# logger.net
KiCad netlist of a schematic drawn in EAGLE
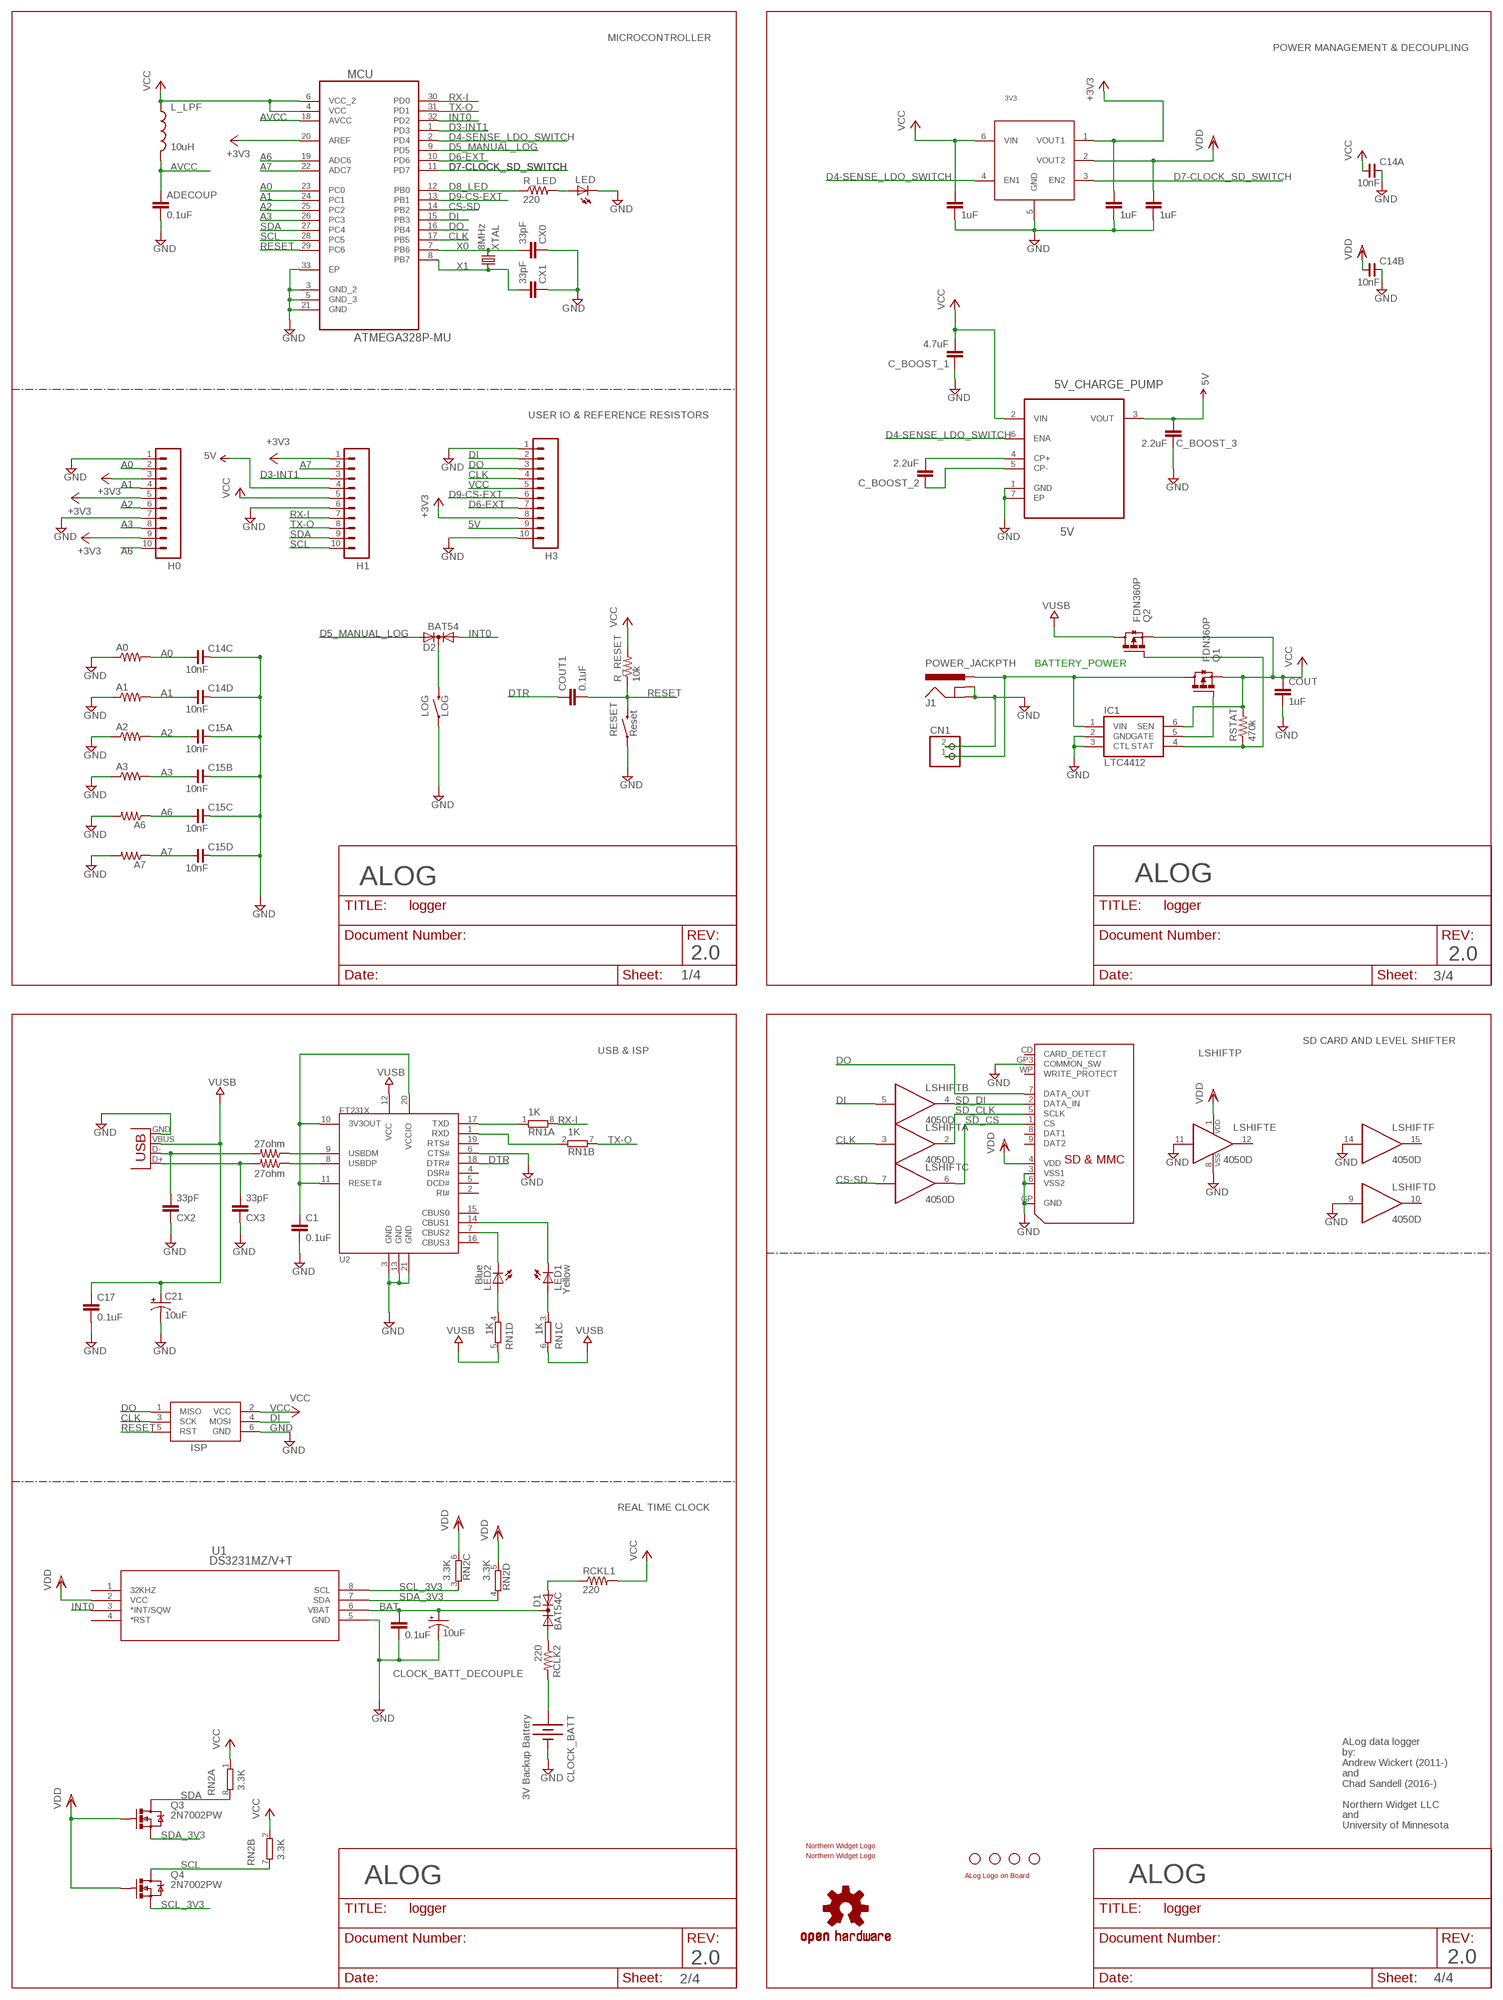
[diagram p0: schematic, sheet 1]

(export (version "E")
  (design (tool "Eeschema 10.0.6"))
  (components
    (comp (ref "3V3")
      (value "MIC5380")
      (footprint "eagle-import:6-TMLF")
      (libsource (lib "eagle-import") (part "MIC5380"))
    )
    (comp (ref "5V_CHARGE_PUMP")
      (value "5V")
      (footprint "eagle-import:SON65P200X200X80-7N")
      (fields (field (name "MPN") "TPS60150DRVR"))
      (libsource (lib "eagle-import") (part "TPS60150DRVR"))
    )
    (comp (ref "A0")
      (value "R-US_0207/10")
      (footprint "eagle-import:0207_10")
      (libsource (lib "eagle-import") (part "resistor_R-US_0207/10"))
    )
    (comp (ref "A1")
      (value "R-US_0207/10")
      (footprint "eagle-import:0207_10")
      (libsource (lib "eagle-import") (part "resistor_R-US_0207/10"))
    )
    (comp (ref "A2")
      (value "R-US_0207/10")
      (footprint "eagle-import:0207_10")
      (libsource (lib "eagle-import") (part "resistor_R-US_0207/10"))
    )
    (comp (ref "A3")
      (value "R-US_0207/10")
      (footprint "eagle-import:0207_10")
      (libsource (lib "eagle-import") (part "resistor_R-US_0207/10"))
    )
    (comp (ref "A6")
      (value "R-US_0207/10")
      (footprint "eagle-import:0207_10")
      (libsource (lib "eagle-import") (part "resistor_R-US_0207/10"))
    )
    (comp (ref "A7")
      (value "R-US_0207/10")
      (footprint "eagle-import:0207_10")
      (libsource (lib "eagle-import") (part "resistor_R-US_0207/10"))
    )
    (comp (ref "ADECOUP")
      (value "0.1uF")
      (footprint "eagle-import:C0603")
      (libsource (lib "eagle-import") (part "resistor_C-EUC0603"))
    )
    (comp (ref "C1")
      (value "0.1uF")
      (footprint "eagle-import:C0603")
      (libsource (lib "eagle-import") (part "resistor_C-EUC0603"))
    )
    (comp (ref "C14")
      (value "10nF")
      (footprint "eagle-import:CECJ-1206")
      (libsource (lib "eagle-import") (part "CCA_ECJ-1206"))
    )
    (comp (ref "C15")
      (value "10nF")
      (footprint "eagle-import:CECJ-1206")
      (libsource (lib "eagle-import") (part "CCA_ECJ-1206"))
    )
    (comp (ref "C17")
      (value "0.1uF")
      (footprint "eagle-import:C0603")
      (libsource (lib "eagle-import") (part "resistor_C-EUC0603"))
    )
    (comp (ref "C21")
      (value "10uF")
      (footprint "eagle-import:EIA3216")
      (libsource (lib "eagle-import") (part "CAP_POL1206"))
    )
    (comp (ref "CLOCK_BATT")
      (value "3V Backup Battery")
      (footprint "eagle-import:BATTCON_12MM_PTH")
      (libsource (lib "eagle-import") (part "BATTERY12PTH"))
    )
    (comp (ref "CLOCK_BATT_DECOUP")
      (value "0.1uF")
      (footprint "eagle-import:C0603")
      (libsource (lib "eagle-import") (part "C-EUC0603"))
    )
    (comp (ref "CLOCK_BATT_DECOUPLE")
      (value "10uF")
      (footprint "eagle-import:EIA3216")
      (libsource (lib "eagle-import") (part "CAP_POL1206"))
    )
    (comp (ref "CLOCK_CIN1")
      (value "1uF")
      (footprint "eagle-import:C0603")
      (libsource (lib "eagle-import") (part "C-EUC0603"))
    )
    (comp (ref "CLOCK_CIN2")
      (value "1uF")
      (footprint "eagle-import:C0603")
      (libsource (lib "eagle-import") (part "C-EUC0603"))
    )
    (comp (ref "CLOCK_CIN3")
      (value "1uF")
      (footprint "eagle-import:C0603")
      (libsource (lib "eagle-import") (part "C-EUC0603"))
    )
    (comp (ref "CN1")
      (value "JST_2PIN-THM")
      (footprint "eagle-import:JST-PH-2-THM")
      (libsource (lib "eagle-import") (part "JST_2PIN-THM"))
    )
    (comp (ref "COUT")
      (value "1uF")
      (footprint "eagle-import:C0603")
      (libsource (lib "eagle-import") (part "C-EUC0603"))
    )
    (comp (ref "COUT1")
      (value "0.1uF")
      (footprint "eagle-import:C0603")
      (libsource (lib "eagle-import") (part "C-EUC0603"))
    )
    (comp (ref "CX0")
      (value "33pF")
      (footprint "eagle-import:C0603")
      (libsource (lib "eagle-import") (part "resistor_C-EUC0603"))
    )
    (comp (ref "CX1")
      (value "33pF")
      (footprint "eagle-import:C0603")
      (libsource (lib "eagle-import") (part "resistor_C-EUC0603"))
    )
    (comp (ref "CX2")
      (value "33pF")
      (footprint "eagle-import:C0603")
      (libsource (lib "eagle-import") (part "resistor_C-EUC0603"))
    )
    (comp (ref "CX3")
      (value "33pF")
      (footprint "eagle-import:C0603")
      (libsource (lib "eagle-import") (part "resistor_C-EUC0603"))
    )
    (comp (ref "C_BOOST_1")
      (value "4.7uF")
      (footprint "eagle-import:C0603")
      (libsource (lib "eagle-import") (part "resistor_C-EUC0603"))
    )
    (comp (ref "C_BOOST_2")
      (value "2.2uF")
      (footprint "eagle-import:C0603")
      (libsource (lib "eagle-import") (part "resistor_C-EUC0603"))
    )
    (comp (ref "C_BOOST_3")
      (value "2.2uF")
      (footprint "eagle-import:C0603")
      (libsource (lib "eagle-import") (part "resistor_C-EUC0603"))
    )
    (comp (ref "D+")
      (value "27ohm")
      (footprint "eagle-import:R0603")
      (libsource (lib "eagle-import") (part "R-US_R0603"))
    )
    (comp (ref "D-")
      (value "27ohm")
      (footprint "eagle-import:R0603")
      (libsource (lib "eagle-import") (part "R-US_R0603"))
    )
    (comp (ref "D1")
      (value "BAT54C")
      (footprint "eagle-import:SOT23C")
      (libsource (lib "eagle-import") (part "DIODE_AC-CA_"))
    )
    (comp (ref "D2")
      (value "BAT54")
      (footprint "eagle-import:SOT23C")
      (libsource (lib "eagle-import") (part "DIODE_AC-CA_"))
    )
    (comp (ref "H0")
      (value "M10-3.5MM")
      (footprint "eagle-import:SCREWTERMINAL-3.5MM-8")
      (libsource (lib "eagle-import") (part "M10-3.5MM"))
    )
    (comp (ref "H1")
      (value "M10-3.5MM")
      (footprint "eagle-import:SCREWTERMINAL-3.5MM-8")
      (libsource (lib "eagle-import") (part "M10-3.5MM"))
    )
    (comp (ref "H3")
      (value "M10-3.5MM")
      (footprint "eagle-import:SCREWTERMINAL-3.5MM-8")
      (libsource (lib "eagle-import") (part "M10-3.5MM"))
    )
    (comp (ref "IC1")
      (value "LTC4412")
      (footprint "eagle-import:TSOT23-6")
      (libsource (lib "eagle-import") (part "LTC4412S6E"))
    )
    (comp (ref "ISP")
      (value "AVRISP-6")
      (footprint "eagle-import:AVRISP")
      (libsource (lib "eagle-import") (part "AVRISP-6"))
    )
    (comp (ref "J1")
      (value "POWER_JACKPTH")
      (footprint "eagle-import:POWER_JACK_PTH")
      (libsource (lib "eagle-import") (part "POWER_JACKPTH"))
    )
    (comp (ref "JP1")
      (value "STAND-OFF")
      (footprint "eagle-import:STAND-OFF")
      (libsource (lib "eagle-import") (part "STAND-OFF"))
    )
    (comp (ref "JP2")
      (value "STAND-OFF")
      (footprint "eagle-import:STAND-OFF")
      (libsource (lib "eagle-import") (part "STAND-OFF"))
    )
    (comp (ref "JP3")
      (value "STAND-OFF")
      (footprint "eagle-import:STAND-OFF")
      (libsource (lib "eagle-import") (part "STAND-OFF"))
    )
    (comp (ref "JP4")
      (value "STAND-OFF")
      (footprint "eagle-import:STAND-OFF")
      (libsource (lib "eagle-import") (part "STAND-OFF"))
    )
    (comp (ref "JP5")
      (value "USB-B")
      (footprint "eagle-import:USB-B-PTH")
      (libsource (lib "eagle-import") (part "USBPTH"))
    )
    (comp (ref "LED")
      (value "LED3MM")
      (footprint "eagle-import:LED3MM")
      (libsource (lib "eagle-import") (part "LED3MM"))
    )
    (comp (ref "LED1")
      (value "Yellow")
      (footprint "eagle-import:LED-0603")
      (libsource (lib "eagle-import") (part "SparkFun-LED_LED0603"))
    )
    (comp (ref "LED2")
      (value "Blue")
      (footprint "eagle-import:LED-0603")
      (libsource (lib "eagle-import") (part "SparkFun-LED_LED0603"))
    )
    (comp (ref "LOG")
      (value "LOG")
      (footprint "eagle-import:TACTILE-PTH")
      (libsource (lib "eagle-import") (part "SWITCH-MOMENTARY-2PTH"))
    )
    (comp (ref "LOGO1")
      (value "OSHW-LOGOM")
      (footprint "eagle-import:OSHW-LOGO-M")
      (libsource (lib "eagle-import") (part "OSHW-LOGOM"))
    )
    (comp (ref "LSHIFT")
      (value "4050D")
      (footprint "eagle-import:SO16")
      (libsource (lib "eagle-import") (part "4050D"))
    )
    (comp (ref "L_LPF")
      (value "10uH")
      (footprint "eagle-import:0805")
      (libsource (lib "eagle-import") (part "INDUCTOR0805"))
    )
    (comp (ref "MCU")
      (value "ATMEGA328P-MU")
      (footprint "eagle-import:QFN50P500X500X100-33N")
      (libsource (lib "eagle-import") (part "ATMEGA328P-MU"))
    )
    (comp (ref "Q1")
      (value "FDN360P")
      (footprint "eagle-import:SUPER-SOT3")
      (libsource (lib "eagle-import") (part "FDN360P"))
    )
    (comp (ref "Q2")
      (value "FDN360P")
      (footprint "eagle-import:SUPER-SOT3")
      (libsource (lib "eagle-import") (part "FDN360P"))
    )
    (comp (ref "Q3")
      (value "2N7002PW")
      (footprint "eagle-import:SOT323")
      (libsource (lib "eagle-import") (part "MOSFET-NCHANNELSOT323"))
    )
    (comp (ref "Q4")
      (value "2N7002PW")
      (footprint "eagle-import:SOT323")
      (libsource (lib "eagle-import") (part "MOSFET-NCHANNELSOT323"))
    )
    (comp (ref "RCKL1")
      (value "220")
      (footprint "eagle-import:R0603")
      (libsource (lib "eagle-import") (part "R-US_R0603"))
    )
    (comp (ref "RCLK2")
      (value "220")
      (footprint "eagle-import:R0603")
      (libsource (lib "eagle-import") (part "R-US_R0603"))
    )
    (comp (ref "RESET")
      (value "Reset")
      (footprint "eagle-import:TACTILE-PTH")
      (libsource (lib "eagle-import") (part "SWITCH-MOMENTARY-2PTH"))
    )
    (comp (ref "RN1")
      (value "1K")
      (footprint "eagle-import:0603-ARC")
      (libsource (lib "eagle-import") (part "4R-N0603-ARC"))
    )
    (comp (ref "RN2")
      (value "3.3K")
      (footprint "eagle-import:0603-ARC")
      (libsource (lib "eagle-import") (part "4R-N0603-ARC"))
    )
    (comp (ref "RSTAT")
      (value "470k")
      (footprint "eagle-import:R0603")
      (libsource (lib "eagle-import") (part "R-US_R0603"))
    )
    (comp (ref "R_LED")
      (value "220")
      (footprint "eagle-import:R0603")
      (libsource (lib "eagle-import") (part "resistor_R-US_R0603"))
    )
    (comp (ref "R_RESET")
      (value "10k")
      (footprint "eagle-import:R0603")
      (libsource (lib "eagle-import") (part "R-US_R0603"))
    )
    (comp (ref "SD")
      (value "SDMMC06132")
      (footprint "eagle-import:06132")
      (libsource (lib "eagle-import") (part "SDMMC06132"))
    )
    (comp (ref "U$1")
      (value "NWLOGO")
      (footprint "eagle-import:NWLOGO")
      (libsource (lib "eagle-import") (part "NWLOGO"))
    )
    (comp (ref "U$2")
      (value "ALOG_LOGO_V1_5.5MM")
      (footprint "eagle-import:ALOG_LOGO_V1_SMALL")
      (libsource (lib "eagle-import") (part "ALOG_LOGO_V1_5.5MM"))
    )
    (comp (ref "U$3")
      (value "NWLOGO_MED")
      (footprint "eagle-import:NWLOGO_MED")
      (libsource (lib "eagle-import") (part "NWLOGO_MED"))
    )
    (comp (ref "U1")
      (value "DS3231MZ/V+T")
      (footprint "eagle-import:21-0041B_8")
      (libsource (lib "eagle-import") (part "DS3231MZ/V+T"))
    )
    (comp (ref "U2")
      (value "FT231X-Q")
      (footprint "eagle-import:QFN20")
      (libsource (lib "eagle-import") (part "FT231X-Q"))
    )
    (comp (ref "XTAL")
      (value "8MHz")
      (footprint "eagle-import:HC49U-V")
      (libsource (lib "eagle-import") (part "CRYSTALHC49UV"))
    )
  )
  (nets
    (net (code "1") (name "+3V3") (class "Default")
      (node (ref "3V3") (pin "1") (pinfunction "VOUT1_1") (pintype "power_in"))
      (node (ref "CLOCK_CIN2") (pin "1") (pinfunction "1_1") (pintype "passive"))
      (node (ref "H0") (pin "3") (pinfunction "3_3") (pintype "passive"))
      (node (ref "H0") (pin "5") (pinfunction "5_5") (pintype "passive"))
      (node (ref "H0") (pin "9") (pinfunction "9_9") (pintype "passive"))
      (node (ref "H1") (pin "1") (pinfunction "1_1") (pintype "passive"))
      (node (ref "H3") (pin "8") (pinfunction "8_8") (pintype "passive"))
      (node (ref "MCU") (pin "20") (pinfunction "AREF_20") (pintype "input"))
    )
    (net (code "2") (name "/A0") (class "Default")
      (node (ref "A0") (pin "2") (pinfunction "2_2") (pintype "passive"))
      (node (ref "C14") (pin "C1") (pinfunction "1_C1") (pintype "passive"))
      (node (ref "H0") (pin "2") (pinfunction "2_2") (pintype "passive"))
      (node (ref "MCU") (pin "23") (pinfunction "PC0_23") (pintype "bidirectional"))
    )
    (net (code "3") (name "/A1") (class "Default")
      (node (ref "A1") (pin "2") (pinfunction "2_2") (pintype "passive"))
      (node (ref "C14") (pin "D1") (pinfunction "1_D1") (pintype "passive"))
      (node (ref "H0") (pin "4") (pinfunction "4_4") (pintype "passive"))
      (node (ref "MCU") (pin "24") (pinfunction "PC1_24") (pintype "bidirectional"))
    )
    (net (code "4") (name "/A2") (class "Default")
      (node (ref "A2") (pin "2") (pinfunction "2_2") (pintype "passive"))
      (node (ref "C15") (pin "A1") (pinfunction "1_A1") (pintype "passive"))
      (node (ref "H0") (pin "6") (pinfunction "6_6") (pintype "passive"))
      (node (ref "MCU") (pin "25") (pinfunction "PC2_25") (pintype "bidirectional"))
    )
    (net (code "5") (name "/A3") (class "Default")
      (node (ref "A3") (pin "2") (pinfunction "2_2") (pintype "passive"))
      (node (ref "C15") (pin "B1") (pinfunction "1_B1") (pintype "passive"))
      (node (ref "H0") (pin "8") (pinfunction "8_8") (pintype "passive"))
      (node (ref "MCU") (pin "26") (pinfunction "PC3_26") (pintype "bidirectional"))
    )
    (net (code "6") (name "/A6") (class "Default")
      (node (ref "A6") (pin "1") (pinfunction "1_1") (pintype "passive"))
      (node (ref "C15") (pin "C1") (pinfunction "1_C1") (pintype "passive"))
      (node (ref "H0") (pin "10") (pinfunction "10_10") (pintype "passive"))
      (node (ref "MCU") (pin "19") (pinfunction "ADC6_19") (pintype "input"))
    )
    (net (code "7") (name "/A7") (class "Default")
      (node (ref "A7") (pin "1") (pinfunction "1_1") (pintype "passive"))
      (node (ref "C15") (pin "D1") (pinfunction "1_D1") (pintype "passive"))
      (node (ref "H1") (pin "2") (pinfunction "2_2") (pintype "passive"))
      (node (ref "MCU") (pin "22") (pinfunction "ADC7_22") (pintype "input"))
    )
    (net (code "8") (name "/AVCC") (class "Default")
      (node (ref "ADECOUP") (pin "1") (pinfunction "1_1") (pintype "passive"))
      (node (ref "L_LPF") (pin "2") (pinfunction "2_2") (pintype "passive"))
      (node (ref "MCU") (pin "18") (pinfunction "AVCC_18") (pintype "power_in"))
    )
    (net (code "9") (name "/BAT") (class "Default")
      (node (ref "CLOCK_BATT_DECOUP") (pin "1") (pinfunction "1_1") (pintype "passive"))
      (node (ref "CLOCK_BATT_DECOUPLE") (pin "A") (pinfunction "+_A") (pintype "passive"))
      (node (ref "D1") (pin "3") (pinfunction "K_3") (pintype "passive"))
      (node (ref "U1") (pin "6") (pinfunction "VBAT_6") (pintype "power_in"))
    )
    (net (code "10") (name "/CLK") (class "Default")
      (node (ref "H3") (pin "4") (pinfunction "4_4") (pintype "passive"))
      (node (ref "ISP") (pin "3") (pinfunction "SCK_3") (pintype "output"))
      (node (ref "LSHIFT") (pin "3") (pinfunction "I_3") (pintype "input"))
      (node (ref "MCU") (pin "17") (pinfunction "PB5_17") (pintype "bidirectional"))
    )
    (net (code "11") (name "/CS-SD") (class "Default")
      (node (ref "LSHIFT") (pin "7") (pinfunction "I_7") (pintype "input"))
      (node (ref "MCU") (pin "14") (pinfunction "PB2_14") (pintype "bidirectional"))
    )
    (net (code "12") (name "/D3-INT1") (class "Default")
      (node (ref "H1") (pin "3") (pinfunction "3_3") (pintype "passive"))
      (node (ref "MCU") (pin "1") (pinfunction "PD3_1") (pintype "bidirectional"))
    )
    (net (code "13") (name "/D4-SENSE_LDO_SWITCH") (class "Default")
      (node (ref "3V3") (pin "4") (pinfunction "EN1_4") (pintype "input"))
      (node (ref "5V_CHARGE_PUMP") (pin "6") (pinfunction "ENA_6") (pintype "input"))
      (node (ref "MCU") (pin "2") (pinfunction "PD4_2") (pintype "bidirectional"))
    )
    (net (code "14") (name "/D5_MANUAL_LOG") (class "Default")
      (node (ref "D2") (pin "2") (pinfunction "A2_2") (pintype "passive"))
      (node (ref "MCU") (pin "9") (pinfunction "PD5_9") (pintype "bidirectional"))
    )
    (net (code "15") (name "/D6-EXT") (class "Default")
      (node (ref "H3") (pin "7") (pinfunction "7_7") (pintype "passive"))
      (node (ref "MCU") (pin "10") (pinfunction "PD6_10") (pintype "bidirectional"))
    )
    (net (code "16") (name "/D7-CLOCK_SD_SWITCH") (class "Default")
      (node (ref "3V3") (pin "3") (pinfunction "EN2_3") (pintype "input"))
      (node (ref "MCU") (pin "11") (pinfunction "PD7_11") (pintype "bidirectional"))
    )
    (net (code "17") (name "/D8_LED") (class "Default")
      (node (ref "MCU") (pin "12") (pinfunction "PB0_12") (pintype "bidirectional"))
      (node (ref "R_LED") (pin "1") (pinfunction "1_1") (pintype "passive"))
    )
    (net (code "18") (name "/D9-CS-EXT") (class "Default")
      (node (ref "H3") (pin "6") (pinfunction "6_6") (pintype "passive"))
      (node (ref "MCU") (pin "13") (pinfunction "PB1_13") (pintype "bidirectional"))
    )
    (net (code "19") (name "/DI") (class "Default")
      (node (ref "H3") (pin "2") (pinfunction "2_2") (pintype "passive"))
      (node (ref "ISP") (pin "4") (pinfunction "MOSI_4") (pintype "output"))
      (node (ref "LSHIFT") (pin "5") (pinfunction "I_5") (pintype "input"))
      (node (ref "MCU") (pin "15") (pinfunction "PB3_15") (pintype "bidirectional"))
    )
    (net (code "20") (name "/DO") (class "Default")
      (node (ref "H3") (pin "3") (pinfunction "3_3") (pintype "passive"))
      (node (ref "ISP") (pin "1") (pinfunction "MISO_1") (pintype "input"))
      (node (ref "MCU") (pin "16") (pinfunction "PB4_16") (pintype "bidirectional"))
      (node (ref "SD") (pin "7") (pinfunction "DATA_OUT_7") (pintype "output"))
    )
    (net (code "21") (name "/DTR") (class "Default")
      (node (ref "COUT1") (pin "1") (pinfunction "1_1") (pintype "passive"))
      (node (ref "U2") (pin "18") (pinfunction "DTR#_18") (pintype "bidirectional"))
    )
    (net (code "22") (name "/INT0") (class "Default")
      (node (ref "D2") (pin "1") (pinfunction "A1_1") (pintype "passive"))
      (node (ref "MCU") (pin "32") (pinfunction "PD2_32") (pintype "bidirectional"))
      (node (ref "U1") (pin "3") (pinfunction "*INT/SQW_3") (pintype "passive"))
    )
    (net (code "23") (name "/RESET") (class "Default")
      (node (ref "COUT1") (pin "2") (pinfunction "2_2") (pintype "passive"))
      (node (ref "ISP") (pin "5") (pinfunction "RST_5") (pintype "output"))
      (node (ref "MCU") (pin "29") (pinfunction "PC6_29") (pintype "bidirectional"))
      (node (ref "RESET") (pin "3") (pinfunction "2_3") (pintype "passive"))
      (node (ref "R_RESET") (pin "1") (pinfunction "1_1") (pintype "passive"))
    )
    (net (code "24") (name "/RX-I") (class "Default")
      (node (ref "H1") (pin "7") (pinfunction "7_7") (pintype "passive"))
      (node (ref "MCU") (pin "30") (pinfunction "PD0_30") (pintype "bidirectional"))
      (node (ref "RN1") (pin "8") (pinfunction "2_8") (pintype "passive"))
    )
    (net (code "25") (name "/SCL") (class "Default")
      (node (ref "H1") (pin "10") (pinfunction "10_10") (pintype "passive"))
      (node (ref "MCU") (pin "28") (pinfunction "PC5_28") (pintype "bidirectional"))
      (node (ref "Q4") (pin "3") (pinfunction "D_3") (pintype "passive"))
      (node (ref "RN2") (pin "7") (pinfunction "2_7") (pintype "passive"))
    )
    (net (code "26") (name "/SCL_3V3") (class "Default")
      (node (ref "Q4") (pin "2") (pinfunction "S_2") (pintype "passive"))
      (node (ref "RN2") (pin "3") (pinfunction "1_3") (pintype "passive"))
      (node (ref "U1") (pin "8") (pinfunction "SCL_8") (pintype "passive"))
    )
    (net (code "27") (name "/SDA") (class "Default")
      (node (ref "H1") (pin "9") (pinfunction "9_9") (pintype "passive"))
      (node (ref "MCU") (pin "27") (pinfunction "PC4_27") (pintype "bidirectional"))
      (node (ref "Q3") (pin "3") (pinfunction "D_3") (pintype "passive"))
      (node (ref "RN2") (pin "8") (pinfunction "2_8") (pintype "passive"))
    )
    (net (code "28") (name "/SDA_3V3") (class "Default")
      (node (ref "Q3") (pin "2") (pinfunction "S_2") (pintype "passive"))
      (node (ref "RN2") (pin "4") (pinfunction "1_4") (pintype "passive"))
      (node (ref "U1") (pin "7") (pinfunction "SDA_7") (pintype "passive"))
    )
    (net (code "29") (name "/SD_CLK") (class "Default")
      (node (ref "LSHIFT") (pin "2") (pinfunction "O_2") (pintype "output"))
      (node (ref "SD") (pin "5") (pinfunction "SCLK_5") (pintype "input"))
    )
    (net (code "30") (name "/SD_CS") (class "Default")
      (node (ref "LSHIFT") (pin "6") (pinfunction "O_6") (pintype "output"))
      (node (ref "SD") (pin "1") (pinfunction "CS_1") (pintype "input"))
    )
    (net (code "31") (name "/SD_DI") (class "Default")
      (node (ref "LSHIFT") (pin "4") (pinfunction "O_4") (pintype "output"))
      (node (ref "SD") (pin "2") (pinfunction "DATA_IN_2") (pintype "input"))
    )
    (net (code "32") (name "/TX-O") (class "Default")
      (node (ref "H1") (pin "8") (pinfunction "8_8") (pintype "passive"))
      (node (ref "MCU") (pin "31") (pinfunction "PD1_31") (pintype "bidirectional"))
      (node (ref "RN1") (pin "7") (pinfunction "2_7") (pintype "passive"))
    )
    (net (code "33") (name "/X0") (class "Default")
      (node (ref "CX0") (pin "2") (pinfunction "2_2") (pintype "passive"))
      (node (ref "MCU") (pin "7") (pinfunction "PB6_7") (pintype "bidirectional"))
      (node (ref "XTAL") (pin "2") (pinfunction "2_2") (pintype "passive"))
    )
    (net (code "34") (name "/X1") (class "Default")
      (node (ref "CX1") (pin "2") (pinfunction "2_2") (pintype "passive"))
      (node (ref "MCU") (pin "8") (pinfunction "PB7_8") (pintype "bidirectional"))
      (node (ref "XTAL") (pin "1") (pinfunction "1_1") (pintype "passive"))
    )
    (net (code "35") (name "5V") (class "Default")
      (node (ref "5V_CHARGE_PUMP") (pin "3") (pinfunction "VOUT_3") (pintype "output"))
      (node (ref "C_BOOST_3") (pin "2") (pinfunction "2_2") (pintype "passive"))
      (node (ref "H1") (pin "4") (pinfunction "4_4") (pintype "passive"))
      (node (ref "H3") (pin "9") (pinfunction "9_9") (pintype "passive"))
    )
    (net (code "36") (name "GND") (class "Default")
      (node (ref "3V3") (pin "5") (pinfunction "GND_5") (pintype "power_in"))
      (node (ref "5V_CHARGE_PUMP") (pin "1") (pinfunction "GND_1") (pintype "passive"))
      (node (ref "5V_CHARGE_PUMP") (pin "7") (pinfunction "EP_7") (pintype "passive"))
      (node (ref "A0") (pin "1") (pinfunction "1_1") (pintype "passive"))
      (node (ref "A1") (pin "1") (pinfunction "1_1") (pintype "passive"))
      (node (ref "A2") (pin "1") (pinfunction "1_1") (pintype "passive"))
      (node (ref "A3") (pin "1") (pinfunction "1_1") (pintype "passive"))
      (node (ref "A6") (pin "2") (pinfunction "2_2") (pintype "passive"))
      (node (ref "A7") (pin "2") (pinfunction "2_2") (pintype "passive"))
      (node (ref "ADECOUP") (pin "2") (pinfunction "2_2") (pintype "passive"))
      (node (ref "C1") (pin "2") (pinfunction "2_2") (pintype "passive"))
      (node (ref "C14") (pin "A2") (pinfunction "2_A2") (pintype "passive"))
      (node (ref "C14") (pin "B2") (pinfunction "2_B2") (pintype "passive"))
      (node (ref "C14") (pin "C2") (pinfunction "2_C2") (pintype "passive"))
      (node (ref "C14") (pin "D2") (pinfunction "2_D2") (pintype "passive"))
      (node (ref "C15") (pin "A2") (pinfunction "2_A2") (pintype "passive"))
      (node (ref "C15") (pin "B2") (pinfunction "2_B2") (pintype "passive"))
      (node (ref "C15") (pin "C2") (pinfunction "2_C2") (pintype "passive"))
      (node (ref "C15") (pin "D2") (pinfunction "2_D2") (pintype "passive"))
      (node (ref "C17") (pin "2") (pinfunction "2_2") (pintype "passive"))
      (node (ref "C21") (pin "C") (pinfunction "-_C") (pintype "passive"))
      (node (ref "CLOCK_BATT") (pin "GND") (pinfunction "-_GND") (pintype "power_in"))
      (node (ref "CLOCK_BATT_DECOUP") (pin "2") (pinfunction "2_2") (pintype "passive"))
      (node (ref "CLOCK_BATT_DECOUPLE") (pin "C") (pinfunction "-_C") (pintype "passive"))
      (node (ref "CLOCK_CIN1") (pin "2") (pinfunction "2_2") (pintype "passive"))
      (node (ref "CLOCK_CIN2") (pin "2") (pinfunction "2_2") (pintype "passive"))
      (node (ref "CLOCK_CIN3") (pin "2") (pinfunction "2_2") (pintype "passive"))
      (node (ref "CN1") (pin "2") (pinfunction "1_2") (pintype "passive"))
      (node (ref "COUT") (pin "2") (pinfunction "2_2") (pintype "passive"))
      (node (ref "CX0") (pin "1") (pinfunction "1_1") (pintype "passive"))
      (node (ref "CX1") (pin "1") (pinfunction "1_1") (pintype "passive"))
      (node (ref "CX2") (pin "1") (pinfunction "1_1") (pintype "passive"))
      (node (ref "CX3") (pin "1") (pinfunction "1_1") (pintype "passive"))
      (node (ref "C_BOOST_1") (pin "1") (pinfunction "1_1") (pintype "passive"))
      (node (ref "C_BOOST_3") (pin "1") (pinfunction "1_1") (pintype "passive"))
      (node (ref "H0") (pin "1") (pinfunction "1_1") (pintype "passive"))
      (node (ref "H0") (pin "7") (pinfunction "7_7") (pintype "passive"))
      (node (ref "H1") (pin "6") (pinfunction "6_6") (pintype "passive"))
      (node (ref "H3") (pin "1") (pinfunction "1_1") (pintype "passive"))
      (node (ref "H3") (pin "10") (pinfunction "10_10") (pintype "passive"))
      (node (ref "IC1") (pin "2") (pinfunction "GND_2") (pintype "passive"))
      (node (ref "IC1") (pin "3") (pinfunction "CTL_3") (pintype "input"))
      (node (ref "ISP") (pin "6") (pinfunction "GND_6") (pintype "power_in"))
      (node (ref "J1") (pin "GND") (pinfunction "GND_GND") (pintype "bidirectional"))
      (node (ref "J1") (pin "GNDBREAK") (pinfunction "GNDBREAK_GNDBREAK") (pintype "bidirectional"))
      (node (ref "JP5") (pin "GND") (pinfunction "GND_GND") (pintype "bidirectional"))
      (node (ref "LED") (pin "K") (pinfunction "C_K") (pintype "passive"))
      (node (ref "LOG") (pin "1") (pinfunction "1_1") (pintype "passive"))
      (node (ref "LSHIFT") (pin "11") (pinfunction "I_11") (pintype "input"))
      (node (ref "LSHIFT") (pin "14") (pinfunction "I_14") (pintype "input"))
      (node (ref "LSHIFT") (pin "8") (pinfunction "VSS_8") (pintype "power_in"))
      (node (ref "LSHIFT") (pin "9") (pinfunction "I_9") (pintype "input"))
      (node (ref "MCU") (pin "21") (pinfunction "GND_21") (pintype "passive"))
      (node (ref "MCU") (pin "3") (pinfunction "GND_2_3") (pintype "passive"))
      (node (ref "MCU") (pin "33") (pinfunction "EP_33") (pintype "passive"))
      (node (ref "MCU") (pin "5") (pinfunction "GND_3_5") (pintype "passive"))
      (node (ref "RESET") (pin "1") (pinfunction "1_1") (pintype "passive"))
      (node (ref "SD") (pin "3") (pinfunction "VSS1_3") (pintype "power_in"))
      (node (ref "SD") (pin "6") (pinfunction "VSS2_6") (pintype "power_in"))
      (node (ref "SD") (pin "GP") (pinfunction "GND_GP") (pintype "power_in"))
      (node (ref "SD") (pin "GP3") (pinfunction "COMMON_SW_GP3") (pintype "passive"))
      (node (ref "U1") (pin "5") (pinfunction "GND_5") (pintype "power_in"))
      (node (ref "U2") (pin "13") (pinfunction "GND_13") (pintype "bidirectional"))
      (node (ref "U2") (pin "21") (pinfunction "GND_21") (pintype "bidirectional"))
      (node (ref "U2") (pin "3") (pinfunction "GND_3") (pintype "bidirectional"))
      (node (ref "U2") (pin "6") (pinfunction "CTS#_6") (pintype "bidirectional"))
    )
    (net (code "37") (name "Net-(5V_CHARGE_PUMP-CP+)") (class "Default")
      (node (ref "5V_CHARGE_PUMP") (pin "4") (pinfunction "CP+_4") (pintype "passive"))
      (node (ref "C_BOOST_2") (pin "2") (pinfunction "2_2") (pintype "passive"))
    )
    (net (code "38") (name "Net-(5V_CHARGE_PUMP-CP-)") (class "Default")
      (node (ref "5V_CHARGE_PUMP") (pin "5") (pinfunction "CP-_5") (pintype "passive"))
      (node (ref "C_BOOST_2") (pin "1") (pinfunction "1_1") (pintype "passive"))
    )
    (net (code "39") (name "Net-(CLOCK_BATT-+)") (class "Default")
      (node (ref "CLOCK_BATT") (pin "VCC@1") (pinfunction "+_VCC@1") (pintype "power_in"))
      (node (ref "RCLK2") (pin "2") (pinfunction "2_2") (pintype "passive"))
    )
    (net (code "40") (name "Net-(CN1-2)") (class "Default")
      (node (ref "CN1") (pin "1") (pinfunction "2_1") (pintype "passive"))
      (node (ref "IC1") (pin "1") (pinfunction "VIN_1") (pintype "input"))
      (node (ref "J1") (pin "PWR") (pinfunction "PWR_PWR") (pintype "bidirectional"))
      (node (ref "Q1") (pin "3") (pinfunction "D_3") (pintype "passive"))
    )
    (net (code "41") (name "Net-(CX2-Pad2)") (class "Default")
      (node (ref "CX2") (pin "2") (pinfunction "2_2") (pintype "passive"))
      (node (ref "D-") (pin "2") (pinfunction "2_2") (pintype "passive"))
      (node (ref "JP5") (pin "D-") (pinfunction "D-_D-") (pintype "bidirectional"))
    )
    (net (code "42") (name "Net-(CX3-Pad2)") (class "Default")
      (node (ref "CX3") (pin "2") (pinfunction "2_2") (pintype "passive"))
      (node (ref "D+") (pin "2") (pinfunction "2_2") (pintype "passive"))
      (node (ref "JP5") (pin "D+") (pinfunction "D+_D+") (pintype "bidirectional"))
    )
    (net (code "43") (name "Net-(D1-A1)") (class "Default")
      (node (ref "D1") (pin "1") (pinfunction "A1_1") (pintype "passive"))
      (node (ref "RCLK2") (pin "1") (pinfunction "1_1") (pintype "passive"))
    )
    (net (code "44") (name "Net-(D1-A2)") (class "Default")
      (node (ref "D1") (pin "2") (pinfunction "A2_2") (pintype "passive"))
      (node (ref "RCKL1") (pin "1") (pinfunction "1_1") (pintype "passive"))
    )
    (net (code "45") (name "Net-(D2-K)") (class "Default")
      (node (ref "D2") (pin "3") (pinfunction "K_3") (pintype "passive"))
      (node (ref "LOG") (pin "3") (pinfunction "2_3") (pintype "passive"))
    )
    (net (code "46") (name "Net-(IC1-GATE)") (class "Default")
      (node (ref "IC1") (pin "5") (pinfunction "GATE_5") (pintype "output"))
      (node (ref "Q1") (pin "1") (pinfunction "G_1") (pintype "passive"))
    )
    (net (code "47") (name "Net-(IC1-STAT)") (class "Default")
      (node (ref "IC1") (pin "4") (pinfunction "STAT_4") (pintype "open_collector"))
      (node (ref "Q2") (pin "1") (pinfunction "G_1") (pintype "passive"))
      (node (ref "RSTAT") (pin "1") (pinfunction "1_1") (pintype "passive"))
    )
    (net (code "48") (name "Net-(LED-PadA)") (class "Default")
      (node (ref "LED") (pin "A") (pinfunction "A_A") (pintype "passive"))
      (node (ref "R_LED") (pin "2") (pinfunction "2_2") (pintype "passive"))
    )
    (net (code "49") (name "Net-(RN1B-1)") (class "Default")
      (node (ref "RN1") (pin "2") (pinfunction "1_2") (pintype "passive"))
      (node (ref "U2") (pin "1") (pinfunction "RXD_1") (pintype "bidirectional"))
    )
    (net (code "50") (name "Net-(RN1C-1)") (class "Default")
      (node (ref "LED1") (pin "A") (pinfunction "A_A") (pintype "passive"))
      (node (ref "RN1") (pin "3") (pinfunction "1_3") (pintype "passive"))
    )
    (net (code "51") (name "Net-(RN1D-1)") (class "Default")
      (node (ref "LED2") (pin "A") (pinfunction "A_A") (pintype "passive"))
      (node (ref "RN1") (pin "4") (pinfunction "1_4") (pintype "passive"))
    )
    (net (code "52") (name "Net-(U2-3V3OUT)") (class "Default")
      (node (ref "C1") (pin "1") (pinfunction "1_1") (pintype "passive"))
      (node (ref "U2") (pin "10") (pinfunction "3V3OUT_10") (pintype "bidirectional"))
      (node (ref "U2") (pin "11") (pinfunction "RESET#_11") (pintype "bidirectional"))
      (node (ref "U2") (pin "20") (pinfunction "VCCIO_20") (pintype "bidirectional"))
    )
    (net (code "53") (name "Net-(U2-CBUS1)") (class "Default")
      (node (ref "LED1") (pin "C") (pinfunction "C_C") (pintype "passive"))
      (node (ref "U2") (pin "14") (pinfunction "CBUS1_14") (pintype "bidirectional"))
    )
    (net (code "54") (name "Net-(U2-CBUS2)") (class "Default")
      (node (ref "LED2") (pin "C") (pinfunction "C_C") (pintype "passive"))
      (node (ref "U2") (pin "7") (pinfunction "CBUS2_7") (pintype "bidirectional"))
    )
    (net (code "55") (name "Net-(U2-TXD)") (class "Default")
      (node (ref "RN1") (pin "1") (pinfunction "1_1") (pintype "passive"))
      (node (ref "U2") (pin "17") (pinfunction "TXD_17") (pintype "bidirectional"))
    )
    (net (code "56") (name "Net-(U2-USBDM)") (class "Default")
      (node (ref "D-") (pin "1") (pinfunction "1_1") (pintype "passive"))
      (node (ref "U2") (pin "9") (pinfunction "USBDM_9") (pintype "bidirectional"))
    )
    (net (code "57") (name "Net-(U2-USBDP)") (class "Default")
      (node (ref "D+") (pin "1") (pinfunction "1_1") (pintype "passive"))
      (node (ref "U2") (pin "8") (pinfunction "USBDP_8") (pintype "bidirectional"))
    )
    (net (code "58") (name "VCC") (class "Default")
      (node (ref "3V3") (pin "6") (pinfunction "VIN_6") (pintype "power_in"))
      (node (ref "5V_CHARGE_PUMP") (pin "2") (pinfunction "VIN_2") (pintype "power_in"))
      (node (ref "C14") (pin "A1") (pinfunction "1_A1") (pintype "passive"))
      (node (ref "CLOCK_CIN1") (pin "1") (pinfunction "1_1") (pintype "passive"))
      (node (ref "COUT") (pin "1") (pinfunction "1_1") (pintype "passive"))
      (node (ref "C_BOOST_1") (pin "2") (pinfunction "2_2") (pintype "passive"))
      (node (ref "H1") (pin "5") (pinfunction "5_5") (pintype "passive"))
      (node (ref "H3") (pin "5") (pinfunction "5_5") (pintype "passive"))
      (node (ref "IC1") (pin "6") (pinfunction "SEN_6") (pintype "input"))
      (node (ref "ISP") (pin "2") (pinfunction "VCC_2") (pintype "power_in"))
      (node (ref "L_LPF") (pin "1") (pinfunction "1_1") (pintype "passive"))
      (node (ref "MCU") (pin "4") (pinfunction "VCC_4") (pintype "power_in"))
      (node (ref "MCU") (pin "6") (pinfunction "VCC_2_6") (pintype "power_in"))
      (node (ref "Q1") (pin "2") (pinfunction "S_2") (pintype "passive"))
      (node (ref "Q2") (pin "2") (pinfunction "S_2") (pintype "passive"))
      (node (ref "RCKL1") (pin "2") (pinfunction "2_2") (pintype "passive"))
      (node (ref "RN2") (pin "1") (pinfunction "1_1") (pintype "passive"))
      (node (ref "RN2") (pin "2") (pinfunction "1_2") (pintype "passive"))
      (node (ref "RSTAT") (pin "2") (pinfunction "2_2") (pintype "passive"))
      (node (ref "R_RESET") (pin "2") (pinfunction "2_2") (pintype "passive"))
    )
    (net (code "59") (name "VDD") (class "Default")
      (node (ref "3V3") (pin "2") (pinfunction "VOUT2_2") (pintype "power_in"))
      (node (ref "C14") (pin "B1") (pinfunction "1_B1") (pintype "passive"))
      (node (ref "CLOCK_CIN3") (pin "1") (pinfunction "1_1") (pintype "passive"))
      (node (ref "LSHIFT") (pin "1") (pinfunction "VDD_1") (pintype "power_in"))
      (node (ref "Q3") (pin "1") (pinfunction "G_1") (pintype "passive"))
      (node (ref "Q4") (pin "1") (pinfunction "G_1") (pintype "passive"))
      (node (ref "RN2") (pin "5") (pinfunction "2_5") (pintype "passive"))
      (node (ref "RN2") (pin "6") (pinfunction "2_6") (pintype "passive"))
      (node (ref "SD") (pin "4") (pinfunction "VDD_4") (pintype "power_in"))
      (node (ref "U1") (pin "2") (pinfunction "VCC_2") (pintype "power_in"))
    )
    (net (code "60") (name "VUSB") (class "Default")
      (node (ref "C17") (pin "1") (pinfunction "1_1") (pintype "passive"))
      (node (ref "C21") (pin "A") (pinfunction "+_A") (pintype "passive"))
      (node (ref "JP5") (pin "VBUS") (pinfunction "VBUS_VBUS") (pintype "bidirectional"))
      (node (ref "Q2") (pin "3") (pinfunction "D_3") (pintype "passive"))
      (node (ref "RN1") (pin "5") (pinfunction "2_5") (pintype "passive"))
      (node (ref "RN1") (pin "6") (pinfunction "2_6") (pintype "passive"))
      (node (ref "U2") (pin "12") (pinfunction "VCC_12") (pintype "bidirectional"))
    )
    (net (code "61") (name "unconnected-(LSHIFTD-O-Pad10)") (class "Default")
      (node (ref "LSHIFT") (pin "10") (pinfunction "O_10") (pintype "output"))
    )
    (net (code "62") (name "unconnected-(LSHIFTE-O-Pad12)") (class "Default")
      (node (ref "LSHIFT") (pin "12") (pinfunction "O_12") (pintype "output"))
    )
    (net (code "63") (name "unconnected-(LSHIFTF-O-Pad15)") (class "Default")
      (node (ref "LSHIFT") (pin "15") (pinfunction "O_15") (pintype "output"))
    )
    (net (code "64") (name "unconnected-(SD-CARD_DETECT-PadCD)") (class "Default")
      (node (ref "SD") (pin "CD") (pinfunction "CARD_DETECT_CD") (pintype "passive"))
    )
    (net (code "65") (name "unconnected-(SD-DAT1-Pad8)") (class "Default")
      (node (ref "SD") (pin "8") (pinfunction "DAT1_8") (pintype "bidirectional"))
    )
    (net (code "66") (name "unconnected-(SD-DAT2-Pad9)") (class "Default")
      (node (ref "SD") (pin "9") (pinfunction "DAT2_9") (pintype "bidirectional"))
    )
    (net (code "67") (name "unconnected-(SD-WRITE_PROTECT-PadWP)") (class "Default")
      (node (ref "SD") (pin "WP") (pinfunction "WRITE_PROTECT_WP") (pintype "passive"))
    )
    (net (code "68") (name "unconnected-(U1-*RST-Pad4)") (class "Default")
      (node (ref "U1") (pin "4") (pinfunction "*RST_4") (pintype "passive"))
    )
    (net (code "69") (name "unconnected-(U1-32KHZ-Pad1)") (class "Default")
      (node (ref "U1") (pin "1") (pinfunction "32KHZ_1") (pintype "passive"))
    )
    (net (code "70") (name "unconnected-(U2-CBUS0-Pad15)") (class "Default")
      (node (ref "U2") (pin "15") (pinfunction "CBUS0_15") (pintype "bidirectional"))
    )
    (net (code "71") (name "unconnected-(U2-CBUS3-Pad16)") (class "Default")
      (node (ref "U2") (pin "16") (pinfunction "CBUS3_16") (pintype "bidirectional"))
    )
    (net (code "72") (name "unconnected-(U2-DCD#-Pad5)") (class "Default")
      (node (ref "U2") (pin "5") (pinfunction "DCD#_5") (pintype "bidirectional"))
    )
    (net (code "73") (name "unconnected-(U2-DSR#-Pad4)") (class "Default")
      (node (ref "U2") (pin "4") (pinfunction "DSR#_4") (pintype "bidirectional"))
    )
    (net (code "74") (name "unconnected-(U2-RI#-Pad2)") (class "Default")
      (node (ref "U2") (pin "2") (pinfunction "RI#_2") (pintype "bidirectional"))
    )
    (net (code "75") (name "unconnected-(U2-RTS#-Pad19)") (class "Default")
      (node (ref "U2") (pin "19") (pinfunction "RTS#_19") (pintype "bidirectional"))
    )
  )
)
